# MainBoard.net
KiCad netlist of a schematic drawn in EAGLE
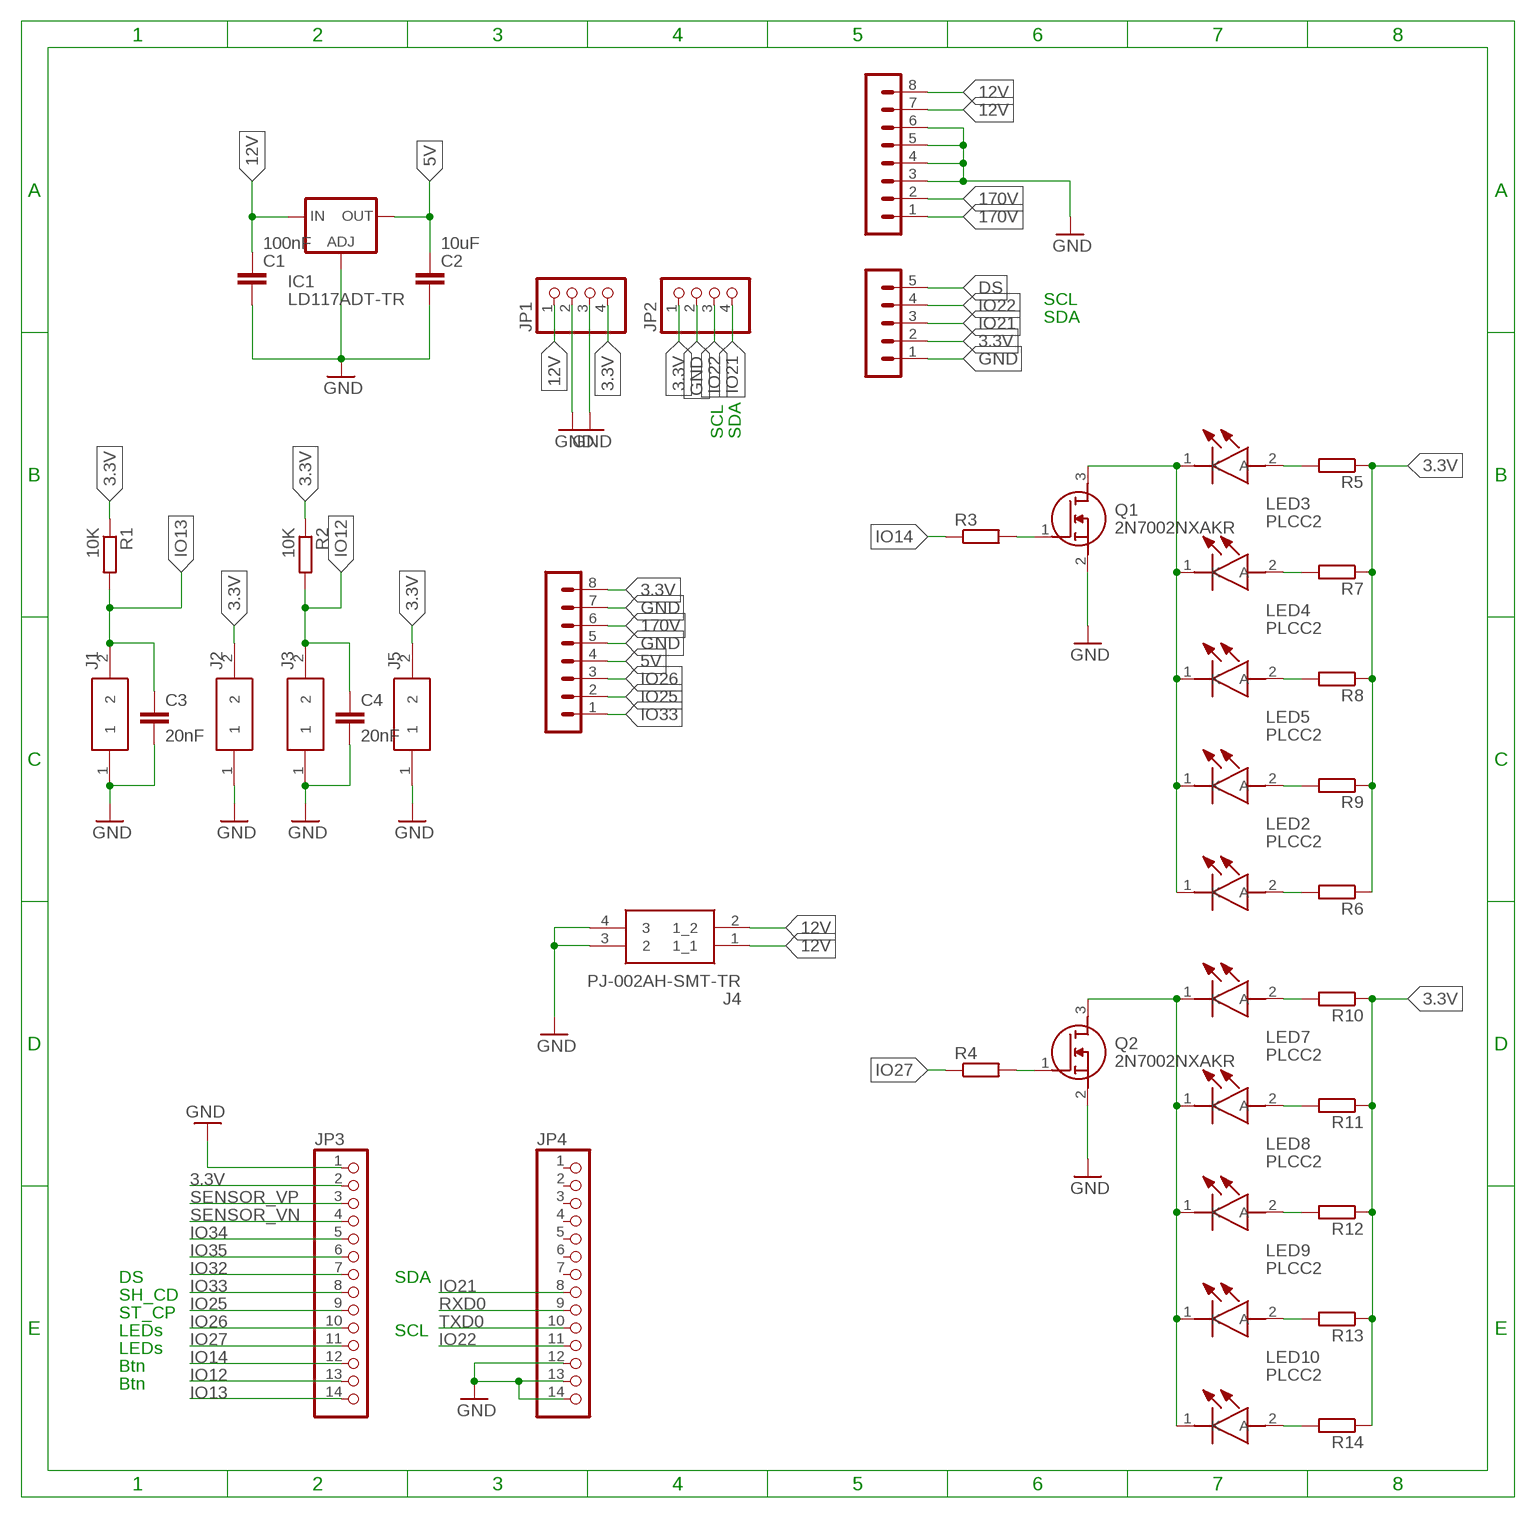
[diagram p0: schematic, sheet 1]

(export (version "E")
  (design (tool "Eeschema 10.0.6"))
  (components
    (comp (ref "C1")
      (value "100nF")
      (footprint "eagle-import:C1206")
      (libsource (lib "eagle-import") (part "C-EU_1206C1206"))
    )
    (comp (ref "C2")
      (value "10uF")
      (footprint "eagle-import:C1206")
      (libsource (lib "eagle-import") (part "C-EU_1206C1206"))
    )
    (comp (ref "C3")
      (value "20nF")
      (footprint "eagle-import:C0805")
      (libsource (lib "eagle-import") (part "C-EU_805C0805"))
    )
    (comp (ref "C4")
      (value "20nF")
      (footprint "eagle-import:C0805")
      (libsource (lib "eagle-import") (part "C-EU_805C0805"))
    )
    (comp (ref "IC1")
      (value "LD117ADT-TR")
      (footprint "eagle-import:DPACK")
      (libsource (lib "eagle-import") (part "LD117A?DT-TR"))
    )
    (comp (ref "J1")
      (value "S2B-NSHSS-TB")
      (footprint "eagle-import:SM02B-NSHSS-TB")
      (fields (field (name "MANUFACTURER_PART_NUMBER") "SM02B-NSHSS-TB(LF)(SN)"))
      (libsource (lib "eagle-import") (part "S2B-NSHSS-TB"))
    )
    (comp (ref "J2")
      (value "S2B-NSHSS-TB")
      (footprint "eagle-import:SM02B-NSHSS-TB")
      (fields (field (name "MANUFACTURER_PART_NUMBER") "SM02B-NSHSS-TB(LF)(SN)"))
      (libsource (lib "eagle-import") (part "S2B-NSHSS-TB"))
    )
    (comp (ref "J3")
      (value "S2B-NSHSS-TB")
      (footprint "eagle-import:SM02B-NSHSS-TB")
      (fields (field (name "MANUFACTURER_PART_NUMBER") "SM02B-NSHSS-TB(LF)(SN)"))
      (libsource (lib "eagle-import") (part "S2B-NSHSS-TB"))
    )
    (comp (ref "J4")
      (value "PJ-002AH-SMT-TR")
      (footprint "eagle-import:PJ-002AH-SMT-TR")
      (fields (field (name "MOUSER_PART_NUMBER") "490-PJ-002AH-SMT-TR"))
      (libsource (lib "eagle-import") (part "PJ-002AH-SMT-TR"))
    )
    (comp (ref "J5")
      (value "S2B-NSHSS-TB")
      (footprint "eagle-import:SM02B-NSHSS-TB")
      (fields (field (name "MANUFACTURER_PART_NUMBER") "SM02B-NSHSS-TB(LF)(SN)"))
      (libsource (lib "eagle-import") (part "S2B-NSHSS-TB"))
    )
    (comp (ref "JP1")
      (value "PINHD-1X4")
      (footprint "eagle-import:1X04")
      (libsource (lib "eagle-import") (part "PINHD-1X4"))
    )
    (comp (ref "JP2")
      (value "PINHD-1X4")
      (footprint "eagle-import:1X04")
      (libsource (lib "eagle-import") (part "PINHD-1X4"))
    )
    (comp (ref "JP3")
      (value "PINHD-1X14")
      (footprint "eagle-import:1X14")
      (libsource (lib "eagle-import") (part "PINHD-1X14"))
    )
    (comp (ref "JP4")
      (value "PINHD-1X14")
      (footprint "eagle-import:1X14")
      (libsource (lib "eagle-import") (part "PINHD-1X14"))
    )
    (comp (ref "LED1")
      (value "PLCC2")
      (footprint "eagle-import:LEDM3528X200N")
      (fields
        (field (name "MANUFACTURER_PART_NUMBER") "ASMT-UWB1-NX302")
        (field (name "MOUSER2_PART_NUMBER") "630-ASMT-UWB1-NX302")
      )
      (libsource (lib "eagle-import") (part "PLCC2"))
    )
    (comp (ref "LED2")
      (value "PLCC2")
      (footprint "eagle-import:LEDM3528X200N")
      (fields
        (field (name "MANUFACTURER_PART_NUMBER") "ASMT-UWB1-NX302")
        (field (name "MOUSER2_PART_NUMBER") "630-ASMT-UWB1-NX302")
      )
      (libsource (lib "eagle-import") (part "PLCC2"))
    )
    (comp (ref "LED3")
      (value "PLCC2")
      (footprint "eagle-import:LEDM3528X200N")
      (fields
        (field (name "MANUFACTURER_PART_NUMBER") "ASMT-UWB1-NX302")
        (field (name "MOUSER2_PART_NUMBER") "630-ASMT-UWB1-NX302")
      )
      (libsource (lib "eagle-import") (part "PLCC2"))
    )
    (comp (ref "LED4")
      (value "PLCC2")
      (footprint "eagle-import:LEDM3528X200N")
      (fields
        (field (name "MANUFACTURER_PART_NUMBER") "ASMT-UWB1-NX302")
        (field (name "MOUSER2_PART_NUMBER") "630-ASMT-UWB1-NX302")
      )
      (libsource (lib "eagle-import") (part "PLCC2"))
    )
    (comp (ref "LED5")
      (value "PLCC2")
      (footprint "eagle-import:LEDM3528X200N")
      (fields
        (field (name "MANUFACTURER_PART_NUMBER") "ASMT-UWB1-NX302")
        (field (name "MOUSER2_PART_NUMBER") "630-ASMT-UWB1-NX302")
      )
      (libsource (lib "eagle-import") (part "PLCC2"))
    )
    (comp (ref "LED6")
      (value "PLCC2")
      (footprint "eagle-import:LEDM3528X200N")
      (fields
        (field (name "MANUFACTURER_PART_NUMBER") "ASMT-UWB1-NX302")
        (field (name "MOUSER2_PART_NUMBER") "630-ASMT-UWB1-NX302")
      )
      (libsource (lib "eagle-import") (part "PLCC2"))
    )
    (comp (ref "LED7")
      (value "PLCC2")
      (footprint "eagle-import:LEDM3528X200N")
      (fields
        (field (name "MANUFACTURER_PART_NUMBER") "ASMT-UWB1-NX302")
        (field (name "MOUSER2_PART_NUMBER") "630-ASMT-UWB1-NX302")
      )
      (libsource (lib "eagle-import") (part "PLCC2"))
    )
    (comp (ref "LED8")
      (value "PLCC2")
      (footprint "eagle-import:LEDM3528X200N")
      (fields
        (field (name "MANUFACTURER_PART_NUMBER") "ASMT-UWB1-NX302")
        (field (name "MOUSER2_PART_NUMBER") "630-ASMT-UWB1-NX302")
      )
      (libsource (lib "eagle-import") (part "PLCC2"))
    )
    (comp (ref "LED9")
      (value "PLCC2")
      (footprint "eagle-import:LEDM3528X200N")
      (fields
        (field (name "MANUFACTURER_PART_NUMBER") "ASMT-UWB1-NX302")
        (field (name "MOUSER2_PART_NUMBER") "630-ASMT-UWB1-NX302")
      )
      (libsource (lib "eagle-import") (part "PLCC2"))
    )
    (comp (ref "LED10")
      (value "PLCC2")
      (footprint "eagle-import:LEDM3528X200N")
      (fields
        (field (name "MANUFACTURER_PART_NUMBER") "ASMT-UWB1-NX302")
        (field (name "MOUSER2_PART_NUMBER") "630-ASMT-UWB1-NX302")
      )
      (libsource (lib "eagle-import") (part "PLCC2"))
    )
    (comp (ref "Q1")
      (value "2N7002NXAKR")
      (footprint "eagle-import:SOT95P230X110-3N")
      (fields (field (name "MOUSER_PART_NUMBER") "771-2N7002NXAKR"))
      (libsource (lib "eagle-import") (part "2N7002NXAKR"))
    )
    (comp (ref "Q2")
      (value "2N7002NXAKR")
      (footprint "eagle-import:SOT95P230X110-3N")
      (fields (field (name "MOUSER_PART_NUMBER") "771-2N7002NXAKR"))
      (libsource (lib "eagle-import") (part "2N7002NXAKR"))
    )
    (comp (ref "R1")
      (value "10K")
      (footprint "eagle-import:R1206")
      (libsource (lib "eagle-import") (part "R-EU_1206R1206"))
    )
    (comp (ref "R2")
      (value "10K")
      (footprint "eagle-import:R1206")
      (libsource (lib "eagle-import") (part "R-EU_1206R1206"))
    )
    (comp (ref "R3")
      (value "R-EU_1206R1206")
      (footprint "eagle-import:R1206")
      (libsource (lib "eagle-import") (part "R-EU_1206R1206"))
    )
    (comp (ref "R4")
      (value "R-EU_1206R1206")
      (footprint "eagle-import:R1206")
      (libsource (lib "eagle-import") (part "R-EU_1206R1206"))
    )
    (comp (ref "R5")
      (value "R-EU_1206R1206")
      (footprint "eagle-import:R1206")
      (libsource (lib "eagle-import") (part "R-EU_1206R1206"))
    )
    (comp (ref "R6")
      (value "R-EU_1206R1206")
      (footprint "eagle-import:R1206")
      (libsource (lib "eagle-import") (part "R-EU_1206R1206"))
    )
    (comp (ref "R7")
      (value "R-EU_1206R1206")
      (footprint "eagle-import:R1206")
      (libsource (lib "eagle-import") (part "R-EU_1206R1206"))
    )
    (comp (ref "R8")
      (value "R-EU_1206R1206")
      (footprint "eagle-import:R1206")
      (libsource (lib "eagle-import") (part "R-EU_1206R1206"))
    )
    (comp (ref "R9")
      (value "R-EU_1206R1206")
      (footprint "eagle-import:R1206")
      (libsource (lib "eagle-import") (part "R-EU_1206R1206"))
    )
    (comp (ref "R10")
      (value "R-EU_1206R1206")
      (footprint "eagle-import:R1206")
      (libsource (lib "eagle-import") (part "R-EU_1206R1206"))
    )
    (comp (ref "R11")
      (value "R-EU_1206R1206")
      (footprint "eagle-import:R1206")
      (libsource (lib "eagle-import") (part "R-EU_1206R1206"))
    )
    (comp (ref "R12")
      (value "R-EU_1206R1206")
      (footprint "eagle-import:R1206")
      (libsource (lib "eagle-import") (part "R-EU_1206R1206"))
    )
    (comp (ref "R13")
      (value "R-EU_1206R1206")
      (footprint "eagle-import:R1206")
      (libsource (lib "eagle-import") (part "R-EU_1206R1206"))
    )
    (comp (ref "R14")
      (value "R-EU_1206R1206")
      (footprint "eagle-import:R1206")
      (libsource (lib "eagle-import") (part "R-EU_1206R1206"))
    )
    (comp (ref "SV1")
      (value "PINHEADER-1X8")
      (footprint "eagle-import:MA08-1")
      (libsource (lib "eagle-import") (part "PINHEADER-1X8"))
    )
    (comp (ref "SV6")
      (value "MA05-1")
      (footprint "eagle-import:MA05-1")
      (libsource (lib "eagle-import") (part "MA05-1"))
    )
    (comp (ref "SV7")
      (value "PINHEADER-1X8")
      (footprint "eagle-import:MA08-1")
      (libsource (lib "eagle-import") (part "PINHEADER-1X8"))
    )
  )
  (nets
    (net (code "1") (name "/IO32") (class "Default")
      (node (ref "JP3") (pin "7") (pinfunction "7_7") (pintype "passive"))
    )
    (net (code "2") (name "/IO34") (class "Default")
      (node (ref "JP3") (pin "5") (pinfunction "5_5") (pintype "passive"))
    )
    (net (code "3") (name "/IO35") (class "Default")
      (node (ref "JP3") (pin "6") (pinfunction "6_6") (pintype "passive"))
    )
    (net (code "4") (name "/RXD0") (class "Default")
      (node (ref "JP4") (pin "9") (pinfunction "9_9") (pintype "passive"))
    )
    (net (code "5") (name "/SENSOR_VN") (class "Default")
      (node (ref "JP3") (pin "4") (pinfunction "4_4") (pintype "passive"))
    )
    (net (code "6") (name "/SENSOR_VP") (class "Default")
      (node (ref "JP3") (pin "3") (pinfunction "3_3") (pintype "passive"))
    )
    (net (code "7") (name "/TXD0") (class "Default")
      (node (ref "JP4") (pin "10") (pinfunction "10_10") (pintype "passive"))
    )
    (net (code "8") (name "3.3V") (class "Default")
      (node (ref "J2") (pin "2") (pinfunction "2_2") (pintype "bidirectional"))
      (node (ref "J5") (pin "2") (pinfunction "2_2") (pintype "bidirectional"))
      (node (ref "JP1") (pin "4") (pinfunction "4_4") (pintype "passive"))
      (node (ref "JP2") (pin "1") (pinfunction "1_1") (pintype "passive"))
      (node (ref "JP3") (pin "2") (pinfunction "2_2") (pintype "passive"))
      (node (ref "R1") (pin "1") (pinfunction "1_1") (pintype "passive"))
      (node (ref "R10") (pin "1") (pinfunction "1_1") (pintype "passive"))
      (node (ref "R11") (pin "1") (pinfunction "1_1") (pintype "passive"))
      (node (ref "R12") (pin "1") (pinfunction "1_1") (pintype "passive"))
      (node (ref "R13") (pin "1") (pinfunction "1_1") (pintype "passive"))
      (node (ref "R14") (pin "1") (pinfunction "1_1") (pintype "passive"))
      (node (ref "R2") (pin "1") (pinfunction "1_1") (pintype "passive"))
      (node (ref "R5") (pin "1") (pinfunction "1_1") (pintype "passive"))
      (node (ref "R6") (pin "1") (pinfunction "1_1") (pintype "passive"))
      (node (ref "R7") (pin "1") (pinfunction "1_1") (pintype "passive"))
      (node (ref "R8") (pin "1") (pinfunction "1_1") (pintype "passive"))
      (node (ref "R9") (pin "1") (pinfunction "1_1") (pintype "passive"))
      (node (ref "SV1") (pin "8") (pinfunction "8_8") (pintype "passive"))
      (node (ref "SV6") (pin "2") (pinfunction "2_2") (pintype "passive"))
    )
    (net (code "9") (name "5V") (class "Default")
      (node (ref "C2") (pin "1") (pinfunction "1_1") (pintype "passive"))
      (node (ref "IC1") (pin "4") (pinfunction "OUT_4") (pintype "passive"))
      (node (ref "SV1") (pin "4") (pinfunction "4_4") (pintype "passive"))
    )
    (net (code "10") (name "12V") (class "Default")
      (node (ref "C1") (pin "1") (pinfunction "1_1") (pintype "passive"))
      (node (ref "IC1") (pin "3") (pinfunction "IN_3") (pintype "input"))
      (node (ref "J4") (pin "1") (pinfunction "1_1_1") (pintype "bidirectional"))
      (node (ref "J4") (pin "2") (pinfunction "1_2_2") (pintype "bidirectional"))
      (node (ref "JP1") (pin "1") (pinfunction "1_1") (pintype "passive"))
      (node (ref "SV7") (pin "7") (pinfunction "7_7") (pintype "passive"))
      (node (ref "SV7") (pin "8") (pinfunction "8_8") (pintype "passive"))
    )
    (net (code "11") (name "170V") (class "Default")
      (node (ref "SV1") (pin "6") (pinfunction "6_6") (pintype "passive"))
      (node (ref "SV7") (pin "1") (pinfunction "1_1") (pintype "passive"))
      (node (ref "SV7") (pin "2") (pinfunction "2_2") (pintype "passive"))
    )
    (net (code "12") (name "DS") (class "Default")
      (node (ref "SV6") (pin "5") (pinfunction "5_5") (pintype "passive"))
    )
    (net (code "13") (name "GND") (class "Default")
      (node (ref "C1") (pin "2") (pinfunction "2_2") (pintype "passive"))
      (node (ref "C2") (pin "2") (pinfunction "2_2") (pintype "passive"))
      (node (ref "C3") (pin "2") (pinfunction "2_2") (pintype "passive"))
      (node (ref "C4") (pin "2") (pinfunction "2_2") (pintype "passive"))
      (node (ref "IC1") (pin "1") (pinfunction "ADJ_1") (pintype "input"))
      (node (ref "J1") (pin "1") (pinfunction "1_1") (pintype "bidirectional"))
      (node (ref "J2") (pin "1") (pinfunction "1_1") (pintype "bidirectional"))
      (node (ref "J3") (pin "1") (pinfunction "1_1") (pintype "bidirectional"))
      (node (ref "J4") (pin "3") (pinfunction "2_3") (pintype "bidirectional"))
      (node (ref "J4") (pin "4") (pinfunction "3_4") (pintype "bidirectional"))
      (node (ref "J5") (pin "1") (pinfunction "1_1") (pintype "bidirectional"))
      (node (ref "JP1") (pin "2") (pinfunction "2_2") (pintype "passive"))
      (node (ref "JP1") (pin "3") (pinfunction "3_3") (pintype "passive"))
      (node (ref "JP2") (pin "2") (pinfunction "2_2") (pintype "passive"))
      (node (ref "JP3") (pin "1") (pinfunction "1_1") (pintype "passive"))
      (node (ref "JP4") (pin "12") (pinfunction "12_12") (pintype "passive"))
      (node (ref "JP4") (pin "13") (pinfunction "13_13") (pintype "passive"))
      (node (ref "JP4") (pin "14") (pinfunction "14_14") (pintype "passive"))
      (node (ref "Q1") (pin "2") (pinfunction "S_2") (pintype "bidirectional"))
      (node (ref "Q2") (pin "2") (pinfunction "S_2") (pintype "bidirectional"))
      (node (ref "SV1") (pin "5") (pinfunction "5_5") (pintype "passive"))
      (node (ref "SV1") (pin "7") (pinfunction "7_7") (pintype "passive"))
      (node (ref "SV6") (pin "1") (pinfunction "1_1") (pintype "passive"))
      (node (ref "SV7") (pin "3") (pinfunction "3_3") (pintype "passive"))
      (node (ref "SV7") (pin "4") (pinfunction "4_4") (pintype "passive"))
      (node (ref "SV7") (pin "5") (pinfunction "5_5") (pintype "passive"))
      (node (ref "SV7") (pin "6") (pinfunction "6_6") (pintype "passive"))
    )
    (net (code "14") (name "IO12") (class "Default")
      (node (ref "C4") (pin "1") (pinfunction "1_1") (pintype "passive"))
      (node (ref "J3") (pin "2") (pinfunction "2_2") (pintype "bidirectional"))
      (node (ref "JP3") (pin "13") (pinfunction "13_13") (pintype "passive"))
      (node (ref "R2") (pin "2") (pinfunction "2_2") (pintype "passive"))
    )
    (net (code "15") (name "IO13") (class "Default")
      (node (ref "C3") (pin "1") (pinfunction "1_1") (pintype "passive"))
      (node (ref "J1") (pin "2") (pinfunction "2_2") (pintype "bidirectional"))
      (node (ref "JP3") (pin "14") (pinfunction "14_14") (pintype "passive"))
      (node (ref "R1") (pin "2") (pinfunction "2_2") (pintype "passive"))
    )
    (net (code "16") (name "IO14") (class "Default")
      (node (ref "JP3") (pin "12") (pinfunction "12_12") (pintype "passive"))
      (node (ref "R3") (pin "1") (pinfunction "1_1") (pintype "passive"))
    )
    (net (code "17") (name "IO21") (class "Default")
      (node (ref "JP2") (pin "4") (pinfunction "4_4") (pintype "passive"))
      (node (ref "JP4") (pin "8") (pinfunction "8_8") (pintype "passive"))
      (node (ref "SV6") (pin "3") (pinfunction "3_3") (pintype "passive"))
    )
    (net (code "18") (name "IO22") (class "Default")
      (node (ref "JP2") (pin "3") (pinfunction "3_3") (pintype "passive"))
      (node (ref "JP4") (pin "11") (pinfunction "11_11") (pintype "passive"))
      (node (ref "SV6") (pin "4") (pinfunction "4_4") (pintype "passive"))
    )
    (net (code "19") (name "IO25") (class "Default")
      (node (ref "JP3") (pin "9") (pinfunction "9_9") (pintype "passive"))
      (node (ref "SV1") (pin "2") (pinfunction "2_2") (pintype "passive"))
    )
    (net (code "20") (name "IO26") (class "Default")
      (node (ref "JP3") (pin "10") (pinfunction "10_10") (pintype "passive"))
      (node (ref "SV1") (pin "3") (pinfunction "3_3") (pintype "passive"))
    )
    (net (code "21") (name "IO27") (class "Default")
      (node (ref "JP3") (pin "11") (pinfunction "11_11") (pintype "passive"))
      (node (ref "R4") (pin "1") (pinfunction "1_1") (pintype "passive"))
    )
    (net (code "22") (name "IO33") (class "Default")
      (node (ref "JP3") (pin "8") (pinfunction "8_8") (pintype "passive"))
      (node (ref "SV1") (pin "1") (pinfunction "1_1") (pintype "passive"))
    )
    (net (code "23") (name "Net-(LED1-A)") (class "Default")
      (node (ref "LED1") (pin "2") (pinfunction "A_2") (pintype "bidirectional"))
      (node (ref "R5") (pin "2") (pinfunction "2_2") (pintype "passive"))
    )
    (net (code "24") (name "Net-(LED1-K)") (class "Default")
      (node (ref "LED1") (pin "1") (pinfunction "K_1") (pintype "bidirectional"))
      (node (ref "LED2") (pin "1") (pinfunction "K_1") (pintype "bidirectional"))
      (node (ref "LED3") (pin "1") (pinfunction "K_1") (pintype "bidirectional"))
      (node (ref "LED4") (pin "1") (pinfunction "K_1") (pintype "bidirectional"))
      (node (ref "LED5") (pin "1") (pinfunction "K_1") (pintype "bidirectional"))
      (node (ref "Q1") (pin "3") (pinfunction "D_3") (pintype "bidirectional"))
    )
    (net (code "25") (name "Net-(LED2-A)") (class "Default")
      (node (ref "LED2") (pin "2") (pinfunction "A_2") (pintype "bidirectional"))
      (node (ref "R6") (pin "2") (pinfunction "2_2") (pintype "passive"))
    )
    (net (code "26") (name "Net-(LED3-A)") (class "Default")
      (node (ref "LED3") (pin "2") (pinfunction "A_2") (pintype "bidirectional"))
      (node (ref "R7") (pin "2") (pinfunction "2_2") (pintype "passive"))
    )
    (net (code "27") (name "Net-(LED4-A)") (class "Default")
      (node (ref "LED4") (pin "2") (pinfunction "A_2") (pintype "bidirectional"))
      (node (ref "R8") (pin "2") (pinfunction "2_2") (pintype "passive"))
    )
    (net (code "28") (name "Net-(LED5-A)") (class "Default")
      (node (ref "LED5") (pin "2") (pinfunction "A_2") (pintype "bidirectional"))
      (node (ref "R9") (pin "2") (pinfunction "2_2") (pintype "passive"))
    )
    (net (code "29") (name "Net-(LED6-A)") (class "Default")
      (node (ref "LED6") (pin "2") (pinfunction "A_2") (pintype "bidirectional"))
      (node (ref "R10") (pin "2") (pinfunction "2_2") (pintype "passive"))
    )
    (net (code "30") (name "Net-(LED7-A)") (class "Default")
      (node (ref "LED7") (pin "2") (pinfunction "A_2") (pintype "bidirectional"))
      (node (ref "R11") (pin "2") (pinfunction "2_2") (pintype "passive"))
    )
    (net (code "31") (name "Net-(LED8-A)") (class "Default")
      (node (ref "LED8") (pin "2") (pinfunction "A_2") (pintype "bidirectional"))
      (node (ref "R12") (pin "2") (pinfunction "2_2") (pintype "passive"))
    )
    (net (code "32") (name "Net-(LED9-A)") (class "Default")
      (node (ref "LED9") (pin "2") (pinfunction "A_2") (pintype "bidirectional"))
      (node (ref "R13") (pin "2") (pinfunction "2_2") (pintype "passive"))
    )
    (net (code "33") (name "Net-(LED10-A)") (class "Default")
      (node (ref "LED10") (pin "2") (pinfunction "A_2") (pintype "bidirectional"))
      (node (ref "R14") (pin "2") (pinfunction "2_2") (pintype "passive"))
    )
    (net (code "34") (name "Net-(LED10-K)") (class "Default")
      (node (ref "LED10") (pin "1") (pinfunction "K_1") (pintype "bidirectional"))
      (node (ref "LED6") (pin "1") (pinfunction "K_1") (pintype "bidirectional"))
      (node (ref "LED7") (pin "1") (pinfunction "K_1") (pintype "bidirectional"))
      (node (ref "LED8") (pin "1") (pinfunction "K_1") (pintype "bidirectional"))
      (node (ref "LED9") (pin "1") (pinfunction "K_1") (pintype "bidirectional"))
      (node (ref "Q2") (pin "3") (pinfunction "D_3") (pintype "bidirectional"))
    )
    (net (code "35") (name "Net-(Q1-G)") (class "Default")
      (node (ref "Q1") (pin "1") (pinfunction "G_1") (pintype "bidirectional"))
      (node (ref "R3") (pin "2") (pinfunction "2_2") (pintype "passive"))
    )
    (net (code "36") (name "Net-(Q2-G)") (class "Default")
      (node (ref "Q2") (pin "1") (pinfunction "G_1") (pintype "bidirectional"))
      (node (ref "R4") (pin "2") (pinfunction "2_2") (pintype "passive"))
    )
    (net (code "37") (name "unconnected-(JP4-Pad1)") (class "Default")
      (node (ref "JP4") (pin "1") (pinfunction "1_1") (pintype "passive"))
    )
    (net (code "38") (name "unconnected-(JP4-Pad2)") (class "Default")
      (node (ref "JP4") (pin "2") (pinfunction "2_2") (pintype "passive"))
    )
    (net (code "39") (name "unconnected-(JP4-Pad3)") (class "Default")
      (node (ref "JP4") (pin "3") (pinfunction "3_3") (pintype "passive"))
    )
    (net (code "40") (name "unconnected-(JP4-Pad4)") (class "Default")
      (node (ref "JP4") (pin "4") (pinfunction "4_4") (pintype "passive"))
    )
    (net (code "41") (name "unconnected-(JP4-Pad5)") (class "Default")
      (node (ref "JP4") (pin "5") (pinfunction "5_5") (pintype "passive"))
    )
    (net (code "42") (name "unconnected-(JP4-Pad6)") (class "Default")
      (node (ref "JP4") (pin "6") (pinfunction "6_6") (pintype "passive"))
    )
    (net (code "43") (name "unconnected-(JP4-Pad7)") (class "Default")
      (node (ref "JP4") (pin "7") (pinfunction "7_7") (pintype "passive"))
    )
  )
)
